# v4_0_Sensor.net
KiCad netlist of a schematic drawn in EAGLE
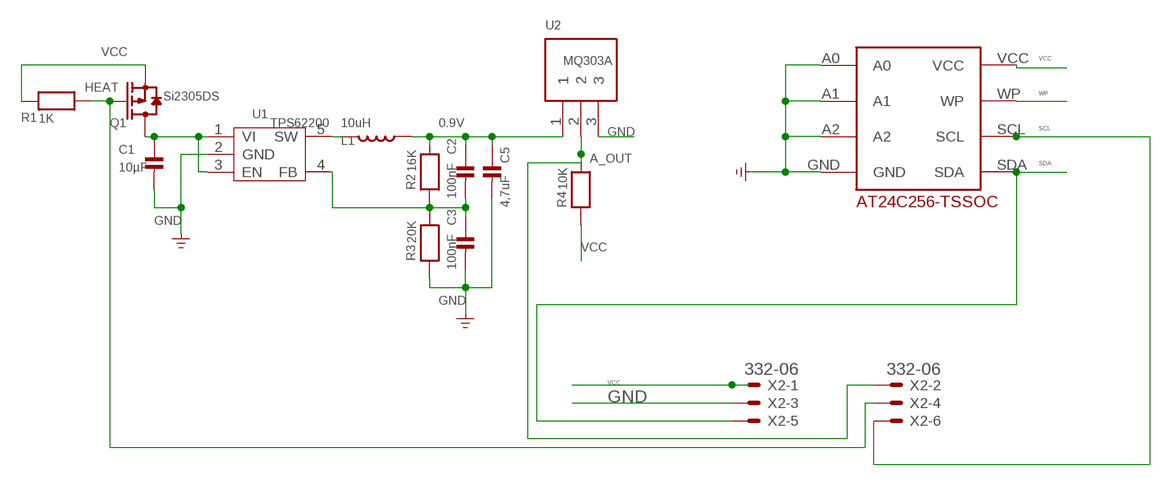
[diagram p0: schematic, sheet 1]

(export (version "E")
  (design (tool "Eeschema 10.0.6"))
  (components
    (comp (ref "C1")
      (value "10µF")
      (footprint "eagle-import:0805")
      (fields (field (name "MPN") "GRM21BR71A106KA73K"))
      (libsource (lib "eagle-import") (part "CAP_CERAMIC0805"))
    )
    (comp (ref "C2")
      (value "100nF")
      (footprint "eagle-import:0805")
      (fields (field (name "MPN") "C0805C104K8RACAUTO"))
      (libsource (lib "eagle-import") (part "CAP_CERAMIC0805"))
    )
    (comp (ref "C3")
      (value "100nF")
      (footprint "eagle-import:0805")
      (fields (field (name "MPN") "C0805C104K8RACAUTO"))
      (libsource (lib "eagle-import") (part "CAP_CERAMIC0805"))
    )
    (comp (ref "C5")
      (value "4,7uF")
      (footprint "eagle-import:0805")
      (fields (field (name "MPN") "0805ZG475ZAT4A"))
      (libsource (lib "eagle-import") (part "CAP_CERAMIC0805"))
    )
    (comp (ref "L1")
      (value "10uH")
      (footprint "eagle-import:PIO73")
      (fields (field (name "MPN") "SDR7045-100M"))
      (libsource (lib "eagle-import") (part "L'PIO73'"))
    )
    (comp (ref "Q1")
      (value "Si2305DS")
      (footprint "eagle-import:SOT23")
      (fields (field (name "MPN") "SI2305DS"))
      (libsource (lib "eagle-import") (part "MOSFET-P'SI2323CDS/SI2305DS{lt}BR{gt}'"))
    )
    (comp (ref "R1")
      (value "1K")
      (footprint "eagle-import:0805")
      (fields (field (name "MPN") "RP73PF2A1K0BTDF"))
      (libsource (lib "eagle-import") (part "RESISTOR0805"))
    )
    (comp (ref "R2")
      (value "16K")
      (footprint "eagle-import:0805")
      (fields (field (name "MPN") "RK73H2ARTTD1602F"))
      (libsource (lib "eagle-import") (part "RESISTOR0805"))
    )
    (comp (ref "R3")
      (value "20K")
      (footprint "eagle-import:0805")
      (fields (field (name "MPN") "RCC080520K0FKEA"))
      (libsource (lib "eagle-import") (part "RESISTOR0805"))
    )
    (comp (ref "R4")
      (value "10K")
      (footprint "eagle-import:0805")
      (fields (field (name "MPN") "RCC080510K0FKEA"))
      (libsource (lib "eagle-import") (part "RESISTOR0805"))
    )
    (comp (ref "U$1")
      (value "DECADE-AT24C256-10TI-2.7")
      (footprint "eagle-import:DECADE-AT24CXX")
      (fields (field (name "MPN") "AT24C256-TSSOC"))
      (libsource (lib "eagle-import") (part "DECADE-AT24C256-10TI-2.7"))
    )
    (comp (ref "U1")
      (value "TPS62200")
      (footprint "eagle-import:SOT23-5")
      (fields (field (name "MPN") "TPS62200DBVR"))
      (libsource (lib "eagle-import") (part "TPS62200DBV"))
    )
    (comp (ref "U2")
      (value "MQ303A")
      (footprint "eagle-import:MQ303A")
      (fields (field (name "MPN") "MQ303B"))
      (libsource (lib "eagle-import") (part "MQ303A"))
    )
    (comp (ref "X2")
      (value "332-06")
      (footprint "eagle-import:332-06")
      (fields (field (name "MPN") "6 Pin - 2mm Dual Row  "))
      (libsource (lib "eagle-import") (part "332-06"))
    )
  )
  (nets
    (net (code "1") (name "/0.9V") (class "Default")
      (node (ref "C2") (pin "1") (pinfunction "P$1_1") (pintype "passive"))
      (node (ref "C5") (pin "1") (pinfunction "P$1_1") (pintype "passive"))
      (node (ref "L1") (pin "2") (pinfunction "2_2") (pintype "passive"))
      (node (ref "R2") (pin "2") (pinfunction "2_2") (pintype "passive"))
      (node (ref "U2") (pin "1") (pinfunction "1_1") (pintype "bidirectional"))
    )
    (net (code "2") (name "/A_OUT") (class "Default")
      (node (ref "R4") (pin "2") (pinfunction "2_2") (pintype "passive"))
      (node (ref "U2") (pin "2") (pinfunction "2_2") (pintype "bidirectional"))
      (node (ref "X2") (pin "2") (pinfunction "S_2") (pintype "passive"))
    )
    (net (code "3") (name "/HEAT") (class "Default")
      (node (ref "Q1") (pin "1") (pinfunction "G_1") (pintype "passive"))
      (node (ref "R1") (pin "2") (pinfunction "2_2") (pintype "passive"))
      (node (ref "X2") (pin "4") (pinfunction "S_4") (pintype "passive"))
    )
    (net (code "4") (name "/SCL") (class "Default")
      (node (ref "U$1") (pin "SCL") (pinfunction "SCL_SCL") (pintype "bidirectional"))
      (node (ref "X2") (pin "6") (pinfunction "S_6") (pintype "passive"))
    )
    (net (code "5") (name "/SDA") (class "Default")
      (node (ref "U$1") (pin "SDA") (pinfunction "SDA_SDA") (pintype "bidirectional"))
      (node (ref "X2") (pin "5") (pinfunction "S_5") (pintype "passive"))
    )
    (net (code "6") (name "/VCC") (class "Default")
      (node (ref "Q1") (pin "2") (pinfunction "S_2") (pintype "passive"))
      (node (ref "R1") (pin "1") (pinfunction "1_1") (pintype "passive"))
      (node (ref "R4") (pin "1") (pinfunction "1_1") (pintype "passive"))
      (node (ref "U$1") (pin "VCC") (pinfunction "VCC_VCC") (pintype "bidirectional"))
      (node (ref "X2") (pin "1") (pinfunction "S_1") (pintype "passive"))
    )
    (net (code "7") (name "/WP") (class "Default")
      (node (ref "U$1") (pin "WP") (pinfunction "WP_WP") (pintype "bidirectional"))
    )
    (net (code "8") (name "GND_POWER") (class "Default")
      (node (ref "C1") (pin "2") (pinfunction "P$2_2") (pintype "passive"))
      (node (ref "C3") (pin "2") (pinfunction "P$2_2") (pintype "passive"))
      (node (ref "C5") (pin "2") (pinfunction "P$2_2") (pintype "passive"))
      (node (ref "R3") (pin "1") (pinfunction "1_1") (pintype "passive"))
      (node (ref "U$1") (pin "A0") (pinfunction "A0_A0") (pintype "bidirectional"))
      (node (ref "U$1") (pin "A1") (pinfunction "A1_A1") (pintype "bidirectional"))
      (node (ref "U$1") (pin "A2") (pinfunction "A2_A2") (pintype "bidirectional"))
      (node (ref "U$1") (pin "GND") (pinfunction "GND_GND") (pintype "bidirectional"))
      (node (ref "U1") (pin "2") (pinfunction "GND_2") (pintype "power_in"))
      (node (ref "U2") (pin "3") (pinfunction "3_3") (pintype "bidirectional"))
      (node (ref "X2") (pin "3") (pinfunction "S_3") (pintype "passive"))
    )
    (net (code "9") (name "Net-(C1-P$1)") (class "Default")
      (node (ref "C1") (pin "1") (pinfunction "P$1_1") (pintype "passive"))
      (node (ref "Q1") (pin "3") (pinfunction "D_3") (pintype "passive"))
      (node (ref "U1") (pin "1") (pinfunction "VI_1") (pintype "input"))
      (node (ref "U1") (pin "3") (pinfunction "EN_3") (pintype "input"))
    )
    (net (code "10") (name "Net-(C2-P$2)") (class "Default")
      (node (ref "C2") (pin "2") (pinfunction "P$2_2") (pintype "passive"))
      (node (ref "C3") (pin "1") (pinfunction "P$1_1") (pintype "passive"))
      (node (ref "R2") (pin "1") (pinfunction "1_1") (pintype "passive"))
      (node (ref "R3") (pin "2") (pinfunction "2_2") (pintype "passive"))
      (node (ref "U1") (pin "4") (pinfunction "FB_4") (pintype "input"))
    )
    (net (code "11") (name "Net-(U1-SW)") (class "Default")
      (node (ref "L1") (pin "1") (pinfunction "1_1") (pintype "passive"))
      (node (ref "U1") (pin "5") (pinfunction "SW_5") (pintype "bidirectional"))
    )
  )
)
